# OSO-SWAT-A1-04.net
KiCad netlist of a schematic drawn in EAGLE
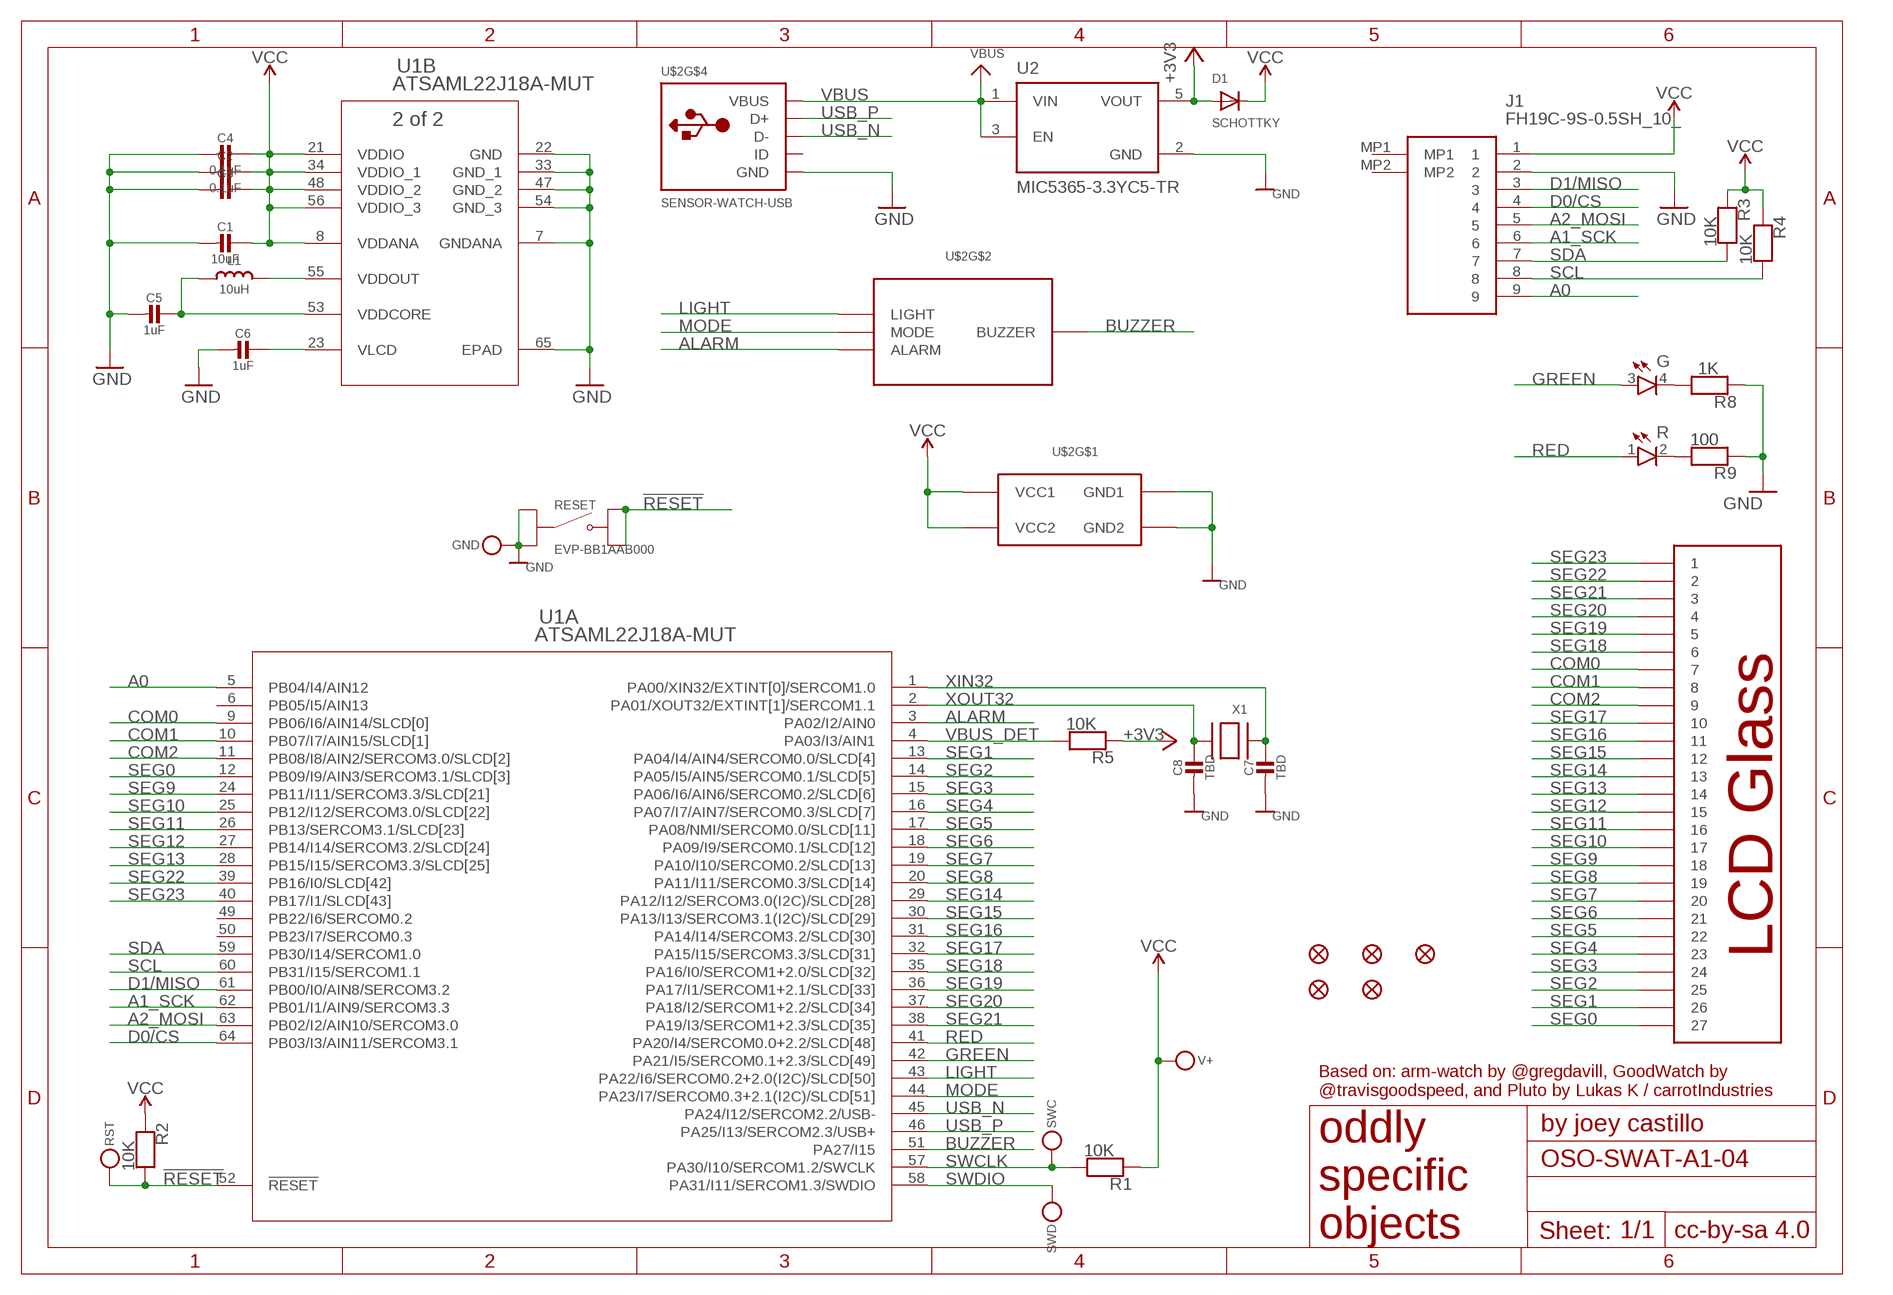
[diagram p0: schematic, sheet 1]

(export (version "E")
  (design (tool "Eeschema 10.0.6"))
  (components
    (comp (ref "C1")
      (value "10uF")
      (footprint "eagle-import:_0603MP")
      (libsource (lib "eagle-import") (part "CAP_CERAMIC_0603MP"))
    )
    (comp (ref "C2")
      (value "0.1uF")
      (footprint "eagle-import:_0603MP")
      (libsource (lib "eagle-import") (part "CAP_CERAMIC_0603MP"))
    )
    (comp (ref "C3")
      (value "0.1uF")
      (footprint "eagle-import:_0603MP")
      (libsource (lib "eagle-import") (part "CAP_CERAMIC_0603MP"))
    )
    (comp (ref "C4")
      (value "0.1uF")
      (footprint "eagle-import:_0603MP")
      (libsource (lib "eagle-import") (part "CAP_CERAMIC_0603MP"))
    )
    (comp (ref "C5")
      (value "1uF")
      (footprint "eagle-import:_0603MP")
      (libsource (lib "eagle-import") (part "CAP_CERAMIC_0603MP"))
    )
    (comp (ref "C6")
      (value "1uF")
      (footprint "eagle-import:_0603MP")
      (libsource (lib "eagle-import") (part "CAP_CERAMIC_0603MP"))
    )
    (comp (ref "C7")
      (value "TBD")
      (footprint "eagle-import:_0402MP")
      (libsource (lib "eagle-import") (part "CAP_CERAMIC_0402MP"))
    )
    (comp (ref "C8")
      (value "TBD")
      (footprint "eagle-import:_0402MP")
      (libsource (lib "eagle-import") (part "CAP_CERAMIC_0402MP"))
    )
    (comp (ref "D1")
      (value "SCHOTTKY")
      (footprint "eagle-import:SOD-323F")
      (libsource (lib "eagle-import") (part "DIODESOD-323F"))
    )
    (comp (ref "FID1")
      (value "FIDUCIAL_1MM")
      (footprint "eagle-import:FIDUCIAL_1MM")
      (libsource (lib "eagle-import") (part "FIDUCIAL_1MM"))
    )
    (comp (ref "FID2")
      (value "FIDUCIAL_1MM")
      (footprint "eagle-import:FIDUCIAL_1MM")
      (libsource (lib "eagle-import") (part "FIDUCIAL_1MM"))
    )
    (comp (ref "FID3")
      (value "FIDUCIAL_1MM")
      (footprint "eagle-import:FIDUCIAL_1MM")
      (fields (field (name "REV") "A"))
      (libsource (lib "eagle-import") (part "FIDUCIAL_1MM"))
    )
    (comp (ref "FID4")
      (value "FIDUCIAL_1MM")
      (footprint "eagle-import:FIDUCIAL_1MM")
      (libsource (lib "eagle-import") (part "FIDUCIAL_1MM"))
    )
    (comp (ref "FID6")
      (value "FIDUCIAL_1MM")
      (footprint "eagle-import:FIDUCIAL_1MM")
      (fields (field (name "REV") "A"))
      (libsource (lib "eagle-import") (part "FIDUCIAL_1MM"))
    )
    (comp (ref "GND")
      (value "MICROBUILDER_TESTPOINTROUND1.5MM")
      (footprint "eagle-import:MICROBUILDER_TESTPOINT_ROUND_1.5MM")
      (libsource (lib "eagle-import") (part "MICROBUILDER_TESTPOINTROUND1.5MM"))
    )
    (comp (ref "J1")
      (value "FH19C-9S-0.5SH_10_")
      (footprint "eagle-import:FH19C9S05SH10")
      (fields
        (field (name "MANUFACTURER_PART_NUMBER") "FH19C-9S-0.5SH(10)")
        (field (name "MOUSER_PART_NUMBER") "798-FH19C9S05SH10")
      )
      (libsource (lib "eagle-import") (part "FH19C-9S-0.5SH_10_"))
    )
    (comp (ref "L1")
      (value "10uH")
      (footprint "eagle-import:MICROBUILDER__0805MP")
      (libsource (lib "eagle-import") (part "MICROBUILDER_INDUCTOR_0805MP"))
    )
    (comp (ref "LED")
      (value "QBLP655-RIG")
      (footprint "eagle-import:LED_QBLP655")
      (fields
        (field (name "DIGI-KEY_PART_NUMBER") "160-2026-1-ND")
        (field (name "MF") "Lite-On Inc.")
        (field (name "MP") "LTST-C235KGKRKT")
      )
      (libsource (lib "eagle-import") (part "QBLP655-RIG"))
    )
    (comp (ref "R1")
      (value "10K")
      (footprint "eagle-import:_0603MP")
      (libsource (lib "eagle-import") (part "RESISTOR_0603MP"))
    )
    (comp (ref "R2")
      (value "10K")
      (footprint "eagle-import:_0603MP")
      (libsource (lib "eagle-import") (part "RESISTOR_0603MP"))
    )
    (comp (ref "R3")
      (value "10K")
      (footprint "eagle-import:_0603MP")
      (libsource (lib "eagle-import") (part "RESISTOR_0603MP"))
    )
    (comp (ref "R4")
      (value "10K")
      (footprint "eagle-import:_0603MP")
      (libsource (lib "eagle-import") (part "RESISTOR_0603MP"))
    )
    (comp (ref "R5")
      (value "10K")
      (footprint "eagle-import:_0603MP")
      (libsource (lib "eagle-import") (part "RESISTOR_0603MP"))
    )
    (comp (ref "R8")
      (value "1K")
      (footprint "eagle-import:_0603MP")
      (libsource (lib "eagle-import") (part "RESISTOR_0603MP"))
    )
    (comp (ref "R9")
      (value "100")
      (footprint "eagle-import:_0603MP")
      (libsource (lib "eagle-import") (part "RESISTOR_0603MP"))
    )
    (comp (ref "RESET")
      (value "EVP-BB1AAB000")
      (footprint "eagle-import:SW_EVP-BB1AAB000")
      (fields
        (field (name "DIGI-KEY_PART_NUMBER") "P124390CT-ND")
        (field (name "MF") "Panasonic Electronic Components")
      )
      (libsource (lib "eagle-import") (part "EVP-BB1AAB000"))
    )
    (comp (ref "RST")
      (value "MICROBUILDER_TESTPOINTROUND1.5MM")
      (footprint "eagle-import:MICROBUILDER_TESTPOINT_ROUND_1.5MM")
      (libsource (lib "eagle-import") (part "MICROBUILDER_TESTPOINTROUND1.5MM"))
    )
    (comp (ref "SWC")
      (value "MICROBUILDER_TESTPOINTROUND1.5MM")
      (footprint "eagle-import:MICROBUILDER_TESTPOINT_ROUND_1.5MM")
      (libsource (lib "eagle-import") (part "MICROBUILDER_TESTPOINTROUND1.5MM"))
    )
    (comp (ref "SWD")
      (value "MICROBUILDER_TESTPOINTROUND1.5MM")
      (footprint "eagle-import:MICROBUILDER_TESTPOINT_ROUND_1.5MM")
      (libsource (lib "eagle-import") (part "MICROBUILDER_TESTPOINTROUND1.5MM"))
    )
    (comp (ref "U$2")
      (value "SENSOR-WATCH-USB")
      (footprint "eagle-import:CASIO-F91W-OUTLINE-USB")
      (libsource (lib "eagle-import") (part "SENSOR-WATCH-USB"))
    )
    (comp (ref "U1")
      (value "ATSAML22J18A-MUT")
      (footprint "eagle-import:QFN64_9X9MC_MCH")
      (fields (field (name "COPYRIGHT") "Copyright (C) 2018 Accelerated Designs. All rights reserved"))
      (libsource (lib "eagle-import") (part "ATSAML22J18A-MUT"))
    )
    (comp (ref "U2")
      (value "MIC5365-3.3YC5-TR")
      (footprint "eagle-import:SOT65P210X110-5N")
      (fields (field (name "DIGI-KEY_PART_NUMBER") "576-3193-1-ND") (field (name "MF") "Microchip"))
      (libsource (lib "eagle-import") (part "MIC5365-3.3YC5-TR"))
    )
    (comp (ref "V+")
      (value "MICROBUILDER_TESTPOINTROUND1.5MM")
      (footprint "eagle-import:MICROBUILDER_TESTPOINT_ROUND_1.5MM")
      (libsource (lib "eagle-import") (part "MICROBUILDER_TESTPOINTROUND1.5MM"))
    )
    (comp (ref "X1")
      (value "XTAL-3.2X1.5")
      (footprint "eagle-import:XTAL3215")
      (libsource (lib "eagle-import") (part "XTAL-3.2X1.5"))
    )
  )
  (nets
    (net (code "1") (name "+3V3") (class "Default")
      (node (ref "D1") (pin "A") (pinfunction "A_A") (pintype "passive"))
      (node (ref "R5") (pin "1") (pinfunction "1_1") (pintype "passive"))
      (node (ref "U2") (pin "5") (pinfunction "VOUT_5") (pintype "output"))
    )
    (net (code "2") (name "/A0") (class "Default")
      (node (ref "J1") (pin "9") (pinfunction "9_9") (pintype "bidirectional"))
      (node (ref "U1") (pin "5") (pinfunction "PB04/I4/AIN12_5") (pintype "bidirectional"))
    )
    (net (code "3") (name "/A1_SCK") (class "Default")
      (node (ref "J1") (pin "6") (pinfunction "6_6") (pintype "bidirectional"))
      (node (ref "U1") (pin "62") (pinfunction "PB01/I1/AIN9/SERCOM3.3_62") (pintype "bidirectional"))
    )
    (net (code "4") (name "/A2_MOSI") (class "Default")
      (node (ref "J1") (pin "5") (pinfunction "5_5") (pintype "bidirectional"))
      (node (ref "U1") (pin "63") (pinfunction "PB02/I2/AIN10/SERCOM3.0_63") (pintype "bidirectional"))
    )
    (net (code "5") (name "/ALARM") (class "Default")
      (node (ref "U$2") (pin "ALARM") (pinfunction "ALARM_ALARM") (pintype "bidirectional"))
      (node (ref "U1") (pin "3") (pinfunction "PA02/I2/AIN0_3") (pintype "bidirectional"))
    )
    (net (code "6") (name "/BUZZER") (class "Default")
      (node (ref "U$2") (pin "BUZZER") (pinfunction "BUZZER_BUZZER") (pintype "bidirectional"))
      (node (ref "U1") (pin "51") (pinfunction "PA27/I15_51") (pintype "bidirectional"))
    )
    (net (code "7") (name "/COM0") (class "Default")
      (node (ref "U$2") (pin "7") (pinfunction "7_7") (pintype "input"))
      (node (ref "U1") (pin "9") (pinfunction "PB06/I6/AIN14/SLCD[0]_9") (pintype "bidirectional"))
    )
    (net (code "8") (name "/COM1") (class "Default")
      (node (ref "U$2") (pin "8") (pinfunction "8_8") (pintype "input"))
      (node (ref "U1") (pin "10") (pinfunction "PB07/I7/AIN15/SLCD[1]_10") (pintype "bidirectional"))
    )
    (net (code "9") (name "/COM2") (class "Default")
      (node (ref "U$2") (pin "9") (pinfunction "9_9") (pintype "input"))
      (node (ref "U1") (pin "11") (pinfunction "PB08/I8/AIN2/SERCOM3.0/SLCD[2]_11") (pintype "bidirectional"))
    )
    (net (code "10") (name "/D0{slash}CS") (class "Default")
      (node (ref "J1") (pin "4") (pinfunction "4_4") (pintype "bidirectional"))
      (node (ref "U1") (pin "64") (pinfunction "PB03/I3/AIN11/SERCOM3.1_64") (pintype "bidirectional"))
    )
    (net (code "11") (name "/D1{slash}MISO") (class "Default")
      (node (ref "J1") (pin "3") (pinfunction "3_3") (pintype "bidirectional"))
      (node (ref "U1") (pin "61") (pinfunction "PB00/I0/AIN8/SERCOM3.2_61") (pintype "bidirectional"))
    )
    (net (code "12") (name "/GREEN") (class "Default")
      (node (ref "LED") (pin "3") (pinfunction "A_3") (pintype "passive"))
      (node (ref "U1") (pin "42") (pinfunction "PA21/I5/SERCOM0.1+2.3/SLCD[49]_42") (pintype "bidirectional"))
    )
    (net (code "13") (name "/LIGHT") (class "Default")
      (node (ref "U$2") (pin "LIGHT") (pinfunction "LIGHT_LIGHT") (pintype "bidirectional"))
      (node (ref "U1") (pin "43") (pinfunction "PA22/I6/SERCOM0.2+2.0(I2C)/SLCD[50]_43") (pintype "bidirectional"))
    )
    (net (code "14") (name "/MODE") (class "Default")
      (node (ref "U$2") (pin "MODE") (pinfunction "MODE_MODE") (pintype "bidirectional"))
      (node (ref "U1") (pin "44") (pinfunction "PA23/I7/SERCOM0.3+2.1(I2C)/SLCD[51]_44") (pintype "bidirectional"))
    )
    (net (code "15") (name "/RED") (class "Default")
      (node (ref "LED") (pin "1") (pinfunction "A_1") (pintype "passive"))
      (node (ref "U1") (pin "41") (pinfunction "PA20/I4/SERCOM0.0+2.2/SLCD[48]_41") (pintype "bidirectional"))
    )
    (net (code "16") (name "/SCL") (class "Default")
      (node (ref "J1") (pin "8") (pinfunction "8_8") (pintype "bidirectional"))
      (node (ref "R4") (pin "2") (pinfunction "2_2") (pintype "passive"))
      (node (ref "U1") (pin "60") (pinfunction "PB31/I15/SERCOM1.1_60") (pintype "bidirectional"))
    )
    (net (code "17") (name "/SDA") (class "Default")
      (node (ref "J1") (pin "7") (pinfunction "7_7") (pintype "bidirectional"))
      (node (ref "R3") (pin "2") (pinfunction "2_2") (pintype "passive"))
      (node (ref "U1") (pin "59") (pinfunction "PB30/I14/SERCOM1.0_59") (pintype "bidirectional"))
    )
    (net (code "18") (name "/SEG0") (class "Default")
      (node (ref "U$2") (pin "27") (pinfunction "27_27") (pintype "input"))
      (node (ref "U1") (pin "12") (pinfunction "PB09/I9/AIN3/SERCOM3.1/SLCD[3]_12") (pintype "bidirectional"))
    )
    (net (code "19") (name "/SEG1") (class "Default")
      (node (ref "U$2") (pin "26") (pinfunction "26_26") (pintype "input"))
      (node (ref "U1") (pin "13") (pinfunction "PA04/I4/AIN4/SERCOM0.0/SLCD[4]_13") (pintype "bidirectional"))
    )
    (net (code "20") (name "/SEG2") (class "Default")
      (node (ref "U$2") (pin "25") (pinfunction "25_25") (pintype "input"))
      (node (ref "U1") (pin "14") (pinfunction "PA05/I5/AIN5/SERCOM0.1/SLCD[5]_14") (pintype "bidirectional"))
    )
    (net (code "21") (name "/SEG3") (class "Default")
      (node (ref "U$2") (pin "24") (pinfunction "24_24") (pintype "input"))
      (node (ref "U1") (pin "15") (pinfunction "PA06/I6/AIN6/SERCOM0.2/SLCD[6]_15") (pintype "bidirectional"))
    )
    (net (code "22") (name "/SEG4") (class "Default")
      (node (ref "U$2") (pin "23") (pinfunction "23_23") (pintype "input"))
      (node (ref "U1") (pin "16") (pinfunction "PA07/I7/AIN7/SERCOM0.3/SLCD[7]_16") (pintype "bidirectional"))
    )
    (net (code "23") (name "/SEG5") (class "Default")
      (node (ref "U$2") (pin "22") (pinfunction "22_22") (pintype "input"))
      (node (ref "U1") (pin "17") (pinfunction "PA08/NMI/SERCOM0.0/SLCD[11]_17") (pintype "bidirectional"))
    )
    (net (code "24") (name "/SEG6") (class "Default")
      (node (ref "U$2") (pin "21") (pinfunction "21_21") (pintype "input"))
      (node (ref "U1") (pin "18") (pinfunction "PA09/I9/SERCOM0.1/SLCD[12]_18") (pintype "bidirectional"))
    )
    (net (code "25") (name "/SEG7") (class "Default")
      (node (ref "U$2") (pin "20") (pinfunction "20_20") (pintype "input"))
      (node (ref "U1") (pin "19") (pinfunction "PA10/I10/SERCOM0.2/SLCD[13]_19") (pintype "bidirectional"))
    )
    (net (code "26") (name "/SEG8") (class "Default")
      (node (ref "U$2") (pin "19") (pinfunction "19_19") (pintype "input"))
      (node (ref "U1") (pin "20") (pinfunction "PA11/I11/SERCOM0.3/SLCD[14]_20") (pintype "bidirectional"))
    )
    (net (code "27") (name "/SEG9") (class "Default")
      (node (ref "U$2") (pin "18") (pinfunction "18_18") (pintype "input"))
      (node (ref "U1") (pin "24") (pinfunction "PB11/I11/SERCOM3.3/SLCD[21]_24") (pintype "bidirectional"))
    )
    (net (code "28") (name "/SEG10") (class "Default")
      (node (ref "U$2") (pin "17") (pinfunction "17_17") (pintype "input"))
      (node (ref "U1") (pin "25") (pinfunction "PB12/I12/SERCOM3.0/SLCD[22]_25") (pintype "bidirectional"))
    )
    (net (code "29") (name "/SEG11") (class "Default")
      (node (ref "U$2") (pin "16") (pinfunction "16_16") (pintype "input"))
      (node (ref "U1") (pin "26") (pinfunction "PB13/SERCOM3.1/SLCD[23]_26") (pintype "bidirectional"))
    )
    (net (code "30") (name "/SEG12") (class "Default")
      (node (ref "U$2") (pin "15") (pinfunction "15_15") (pintype "input"))
      (node (ref "U1") (pin "27") (pinfunction "PB14/I14/SERCOM3.2/SLCD[24]_27") (pintype "bidirectional"))
    )
    (net (code "31") (name "/SEG13") (class "Default")
      (node (ref "U$2") (pin "14") (pinfunction "14_14") (pintype "input"))
      (node (ref "U1") (pin "28") (pinfunction "PB15/I15/SERCOM3.3/SLCD[25]_28") (pintype "bidirectional"))
    )
    (net (code "32") (name "/SEG14") (class "Default")
      (node (ref "U$2") (pin "13") (pinfunction "13_13") (pintype "input"))
      (node (ref "U1") (pin "29") (pinfunction "PA12/I12/SERCOM3.0(I2C)/SLCD[28]_29") (pintype "bidirectional"))
    )
    (net (code "33") (name "/SEG15") (class "Default")
      (node (ref "U$2") (pin "12") (pinfunction "12_12") (pintype "input"))
      (node (ref "U1") (pin "30") (pinfunction "PA13/I13/SERCOM3.1(I2C)/SLCD[29]_30") (pintype "bidirectional"))
    )
    (net (code "34") (name "/SEG16") (class "Default")
      (node (ref "U$2") (pin "11") (pinfunction "11_11") (pintype "input"))
      (node (ref "U1") (pin "31") (pinfunction "PA14/I14/SERCOM3.2/SLCD[30]_31") (pintype "bidirectional"))
    )
    (net (code "35") (name "/SEG17") (class "Default")
      (node (ref "U$2") (pin "10") (pinfunction "10_10") (pintype "input"))
      (node (ref "U1") (pin "32") (pinfunction "PA15/I15/SERCOM3.3/SLCD[31]_32") (pintype "bidirectional"))
    )
    (net (code "36") (name "/SEG18") (class "Default")
      (node (ref "U$2") (pin "6") (pinfunction "6_6") (pintype "input"))
      (node (ref "U1") (pin "35") (pinfunction "PA16/I0/SERCOM1+2.0/SLCD[32]_35") (pintype "bidirectional"))
    )
    (net (code "37") (name "/SEG19") (class "Default")
      (node (ref "U$2") (pin "5") (pinfunction "5_5") (pintype "input"))
      (node (ref "U1") (pin "36") (pinfunction "PA17/I1/SERCOM1+2.1/SLCD[33]_36") (pintype "bidirectional"))
    )
    (net (code "38") (name "/SEG20") (class "Default")
      (node (ref "U$2") (pin "4") (pinfunction "4_4") (pintype "input"))
      (node (ref "U1") (pin "37") (pinfunction "PA18/I2/SERCOM1+2.2/SLCD[34]_37") (pintype "bidirectional"))
    )
    (net (code "39") (name "/SEG21") (class "Default")
      (node (ref "U$2") (pin "3") (pinfunction "3_3") (pintype "input"))
      (node (ref "U1") (pin "38") (pinfunction "PA19/I3/SERCOM1+2.3/SLCD[35]_38") (pintype "bidirectional"))
    )
    (net (code "40") (name "/SEG22") (class "Default")
      (node (ref "U$2") (pin "2") (pinfunction "2_2") (pintype "input"))
      (node (ref "U1") (pin "39") (pinfunction "PB16/I0/SLCD[42]_39") (pintype "bidirectional"))
    )
    (net (code "41") (name "/SEG23") (class "Default")
      (node (ref "U$2") (pin "1") (pinfunction "1_1") (pintype "input"))
      (node (ref "U1") (pin "40") (pinfunction "PB17/I1/SLCD[43]_40") (pintype "bidirectional"))
    )
    (net (code "42") (name "/SWCLK") (class "Default")
      (node (ref "R1") (pin "2") (pinfunction "2_2") (pintype "passive"))
      (node (ref "SWC") (pin "P$1") (pinfunction "P$1_P$1") (pintype "bidirectional"))
      (node (ref "U1") (pin "57") (pinfunction "PA30/I10/SERCOM1.2/SWCLK_57") (pintype "bidirectional"))
    )
    (net (code "43") (name "/SWDIO") (class "Default")
      (node (ref "SWD") (pin "P$1") (pinfunction "P$1_P$1") (pintype "bidirectional"))
      (node (ref "U1") (pin "58") (pinfunction "PA31/I11/SERCOM1.3/SWDIO_58") (pintype "bidirectional"))
    )
    (net (code "44") (name "/USB_N") (class "Default")
      (node (ref "U$2") (pin "USB_N") (pinfunction "D-_USB_N") (pintype "bidirectional"))
      (node (ref "U1") (pin "45") (pinfunction "PA24/I12/SERCOM2.2/USB-_45") (pintype "bidirectional"))
    )
    (net (code "45") (name "/USB_P") (class "Default")
      (node (ref "U$2") (pin "USB_P") (pinfunction "D+_USB_P") (pintype "bidirectional"))
      (node (ref "U1") (pin "46") (pinfunction "PA25/I13/SERCOM2.3/USB+_46") (pintype "bidirectional"))
    )
    (net (code "46") (name "/VBUS_DET") (class "Default")
      (node (ref "R5") (pin "2") (pinfunction "2_2") (pintype "passive"))
      (node (ref "U1") (pin "4") (pinfunction "PA03/I3/AIN1_4") (pintype "bidirectional"))
    )
    (net (code "47") (name "/XIN32") (class "Default")
      (node (ref "C7") (pin "1") (pinfunction "1_1") (pintype "passive"))
      (node (ref "U1") (pin "1") (pinfunction "PA00/XIN32/EXTINT[0]/SERCOM1.0_1") (pintype "bidirectional"))
      (node (ref "X1") (pin "P$1") (pinfunction "P$1_P$1") (pintype "bidirectional"))
    )
    (net (code "48") (name "/XOUT32") (class "Default")
      (node (ref "C8") (pin "1") (pinfunction "1_1") (pintype "passive"))
      (node (ref "U1") (pin "2") (pinfunction "PA01/XOUT32/EXTINT[1]/SERCOM1.1_2") (pintype "bidirectional"))
      (node (ref "X1") (pin "P$2") (pinfunction "P$2_P$2") (pintype "bidirectional"))
    )
    (net (code "49") (name "/~{RESET}") (class "Default")
      (node (ref "R2") (pin "2") (pinfunction "2_2") (pintype "passive"))
      (node (ref "RESET") (pin "B1") (pinfunction "B1_B1") (pintype "passive"))
      (node (ref "RESET") (pin "B2") (pinfunction "B2_B2") (pintype "passive"))
      (node (ref "RST") (pin "P$1") (pinfunction "P$1_P$1") (pintype "bidirectional"))
      (node (ref "U1") (pin "52") (pinfunction "~{RESET}_52") (pintype "bidirectional"))
    )
    (net (code "50") (name "GND") (class "Default")
      (node (ref "C1") (pin "2") (pinfunction "2_2") (pintype "passive"))
      (node (ref "C2") (pin "2") (pinfunction "2_2") (pintype "passive"))
      (node (ref "C3") (pin "2") (pinfunction "2_2") (pintype "passive"))
      (node (ref "C4") (pin "2") (pinfunction "2_2") (pintype "passive"))
      (node (ref "C5") (pin "2") (pinfunction "2_2") (pintype "passive"))
      (node (ref "C6") (pin "2") (pinfunction "2_2") (pintype "passive"))
      (node (ref "C7") (pin "2") (pinfunction "2_2") (pintype "passive"))
      (node (ref "C8") (pin "2") (pinfunction "2_2") (pintype "passive"))
      (node (ref "GND") (pin "P$1") (pinfunction "P$1_P$1") (pintype "bidirectional"))
      (node (ref "J1") (pin "2") (pinfunction "2_2") (pintype "bidirectional"))
      (node (ref "R8") (pin "1") (pinfunction "1_1") (pintype "passive"))
      (node (ref "R9") (pin "1") (pinfunction "1_1") (pintype "passive"))
      (node (ref "RESET") (pin "A1") (pinfunction "A1_A1") (pintype "passive"))
      (node (ref "RESET") (pin "A2") (pinfunction "A2_A2") (pintype "passive"))
      (node (ref "U$2") (pin "GND") (pinfunction "GND_GND") (pintype "power_in"))
      (node (ref "U$2") (pin "GND1") (pinfunction "GND1_GND1") (pintype "bidirectional"))
      (node (ref "U$2") (pin "GND2") (pinfunction "GND2_GND2") (pintype "bidirectional"))
      (node (ref "U1") (pin "22") (pinfunction "GND_22") (pintype "passive"))
      (node (ref "U1") (pin "33") (pinfunction "GND_1_33") (pintype "passive"))
      (node (ref "U1") (pin "47") (pinfunction "GND_2_47") (pintype "passive"))
      (node (ref "U1") (pin "54") (pinfunction "GND_3_54") (pintype "passive"))
      (node (ref "U1") (pin "65") (pinfunction "EPAD_65") (pintype "passive"))
      (node (ref "U1") (pin "7") (pinfunction "GNDANA_7") (pintype "passive"))
      (node (ref "U2") (pin "2") (pinfunction "GND_2") (pintype "power_in"))
    )
    (net (code "51") (name "Net-(LEDA-C)") (class "Default")
      (node (ref "LED") (pin "2") (pinfunction "C_2") (pintype "passive"))
      (node (ref "R9") (pin "2") (pinfunction "2_2") (pintype "passive"))
    )
    (net (code "52") (name "Net-(LEDB-C)") (class "Default")
      (node (ref "LED") (pin "4") (pinfunction "C_4") (pintype "passive"))
      (node (ref "R8") (pin "2") (pinfunction "2_2") (pintype "passive"))
    )
    (net (code "53") (name "Net-(U1B-VDDCORE)") (class "Default")
      (node (ref "C5") (pin "1") (pinfunction "1_1") (pintype "passive"))
      (node (ref "L1") (pin "1") (pinfunction "1_1") (pintype "passive"))
      (node (ref "U1") (pin "53") (pinfunction "VDDCORE_53") (pintype "power_in"))
    )
    (net (code "54") (name "Net-(U1B-VDDOUT)") (class "Default")
      (node (ref "L1") (pin "2") (pinfunction "2_2") (pintype "passive"))
      (node (ref "U1") (pin "55") (pinfunction "VDDOUT_55") (pintype "output"))
    )
    (net (code "55") (name "Net-(U1B-VLCD)") (class "Default")
      (node (ref "C6") (pin "1") (pinfunction "1_1") (pintype "passive"))
      (node (ref "U1") (pin "23") (pinfunction "VLCD_23") (pintype "passive"))
    )
    (net (code "56") (name "VBUS") (class "Default")
      (node (ref "U$2") (pin "VBUS") (pinfunction "VBUS_VBUS") (pintype "power_in"))
      (node (ref "U2") (pin "1") (pinfunction "VIN_1") (pintype "input"))
      (node (ref "U2") (pin "3") (pinfunction "EN_3") (pintype "input"))
    )
    (net (code "57") (name "VCC") (class "Default")
      (node (ref "C1") (pin "1") (pinfunction "1_1") (pintype "passive"))
      (node (ref "C2") (pin "1") (pinfunction "1_1") (pintype "passive"))
      (node (ref "C3") (pin "1") (pinfunction "1_1") (pintype "passive"))
      (node (ref "C4") (pin "1") (pinfunction "1_1") (pintype "passive"))
      (node (ref "D1") (pin "C") (pinfunction "C_C") (pintype "passive"))
      (node (ref "J1") (pin "1") (pinfunction "1_1") (pintype "bidirectional"))
      (node (ref "R1") (pin "1") (pinfunction "1_1") (pintype "passive"))
      (node (ref "R2") (pin "1") (pinfunction "1_1") (pintype "passive"))
      (node (ref "R3") (pin "1") (pinfunction "1_1") (pintype "passive"))
      (node (ref "R4") (pin "1") (pinfunction "1_1") (pintype "passive"))
      (node (ref "U$2") (pin "VCC1") (pinfunction "VCC1_VCC1") (pintype "bidirectional"))
      (node (ref "U$2") (pin "VCC2") (pinfunction "VCC2_VCC2") (pintype "bidirectional"))
      (node (ref "U1") (pin "21") (pinfunction "VDDIO_21") (pintype "power_in"))
      (node (ref "U1") (pin "34") (pinfunction "VDDIO_1_34") (pintype "power_in"))
      (node (ref "U1") (pin "48") (pinfunction "VDDIO_2_48") (pintype "power_in"))
      (node (ref "U1") (pin "56") (pinfunction "VDDIO_3_56") (pintype "power_in"))
      (node (ref "U1") (pin "8") (pinfunction "VDDANA_8") (pintype "power_in"))
      (node (ref "V+") (pin "P$1") (pinfunction "P$1_P$1") (pintype "bidirectional"))
    )
    (net (code "58") (name "unconnected-(J1-PadMP1)") (class "Default")
      (node (ref "J1") (pin "MP1") (pinfunction "MP1_MP1") (pintype "bidirectional"))
    )
    (net (code "59") (name "unconnected-(J1-PadMP2)") (class "Default")
      (node (ref "J1") (pin "MP2") (pinfunction "MP2_MP2") (pintype "bidirectional"))
    )
    (net (code "60") (name "unconnected-(U$2D-ID-PadUSB_ID)") (class "Default")
      (node (ref "U$2") (pin "USB_ID") (pinfunction "ID_USB_ID") (pintype "bidirectional"))
    )
    (net (code "61") (name "unconnected-(U1A-PB05{slash}I5{slash}AIN13-Pad6)") (class "Default")
      (node (ref "U1") (pin "6") (pinfunction "PB05/I5/AIN13_6") (pintype "bidirectional"))
    )
    (net (code "62") (name "unconnected-(U1A-PB22{slash}I6{slash}SERCOM0.2-Pad49)") (class "Default")
      (node (ref "U1") (pin "49") (pinfunction "PB22/I6/SERCOM0.2_49") (pintype "bidirectional"))
    )
    (net (code "63") (name "unconnected-(U1A-PB23{slash}I7{slash}SERCOM0.3-Pad50)") (class "Default")
      (node (ref "U1") (pin "50") (pinfunction "PB23/I7/SERCOM0.3_50") (pintype "bidirectional"))
    )
  )
)
